# HIGHSPEED_v0_SF2-POWER.net
KiCad netlist of a schematic drawn in Altium Designer
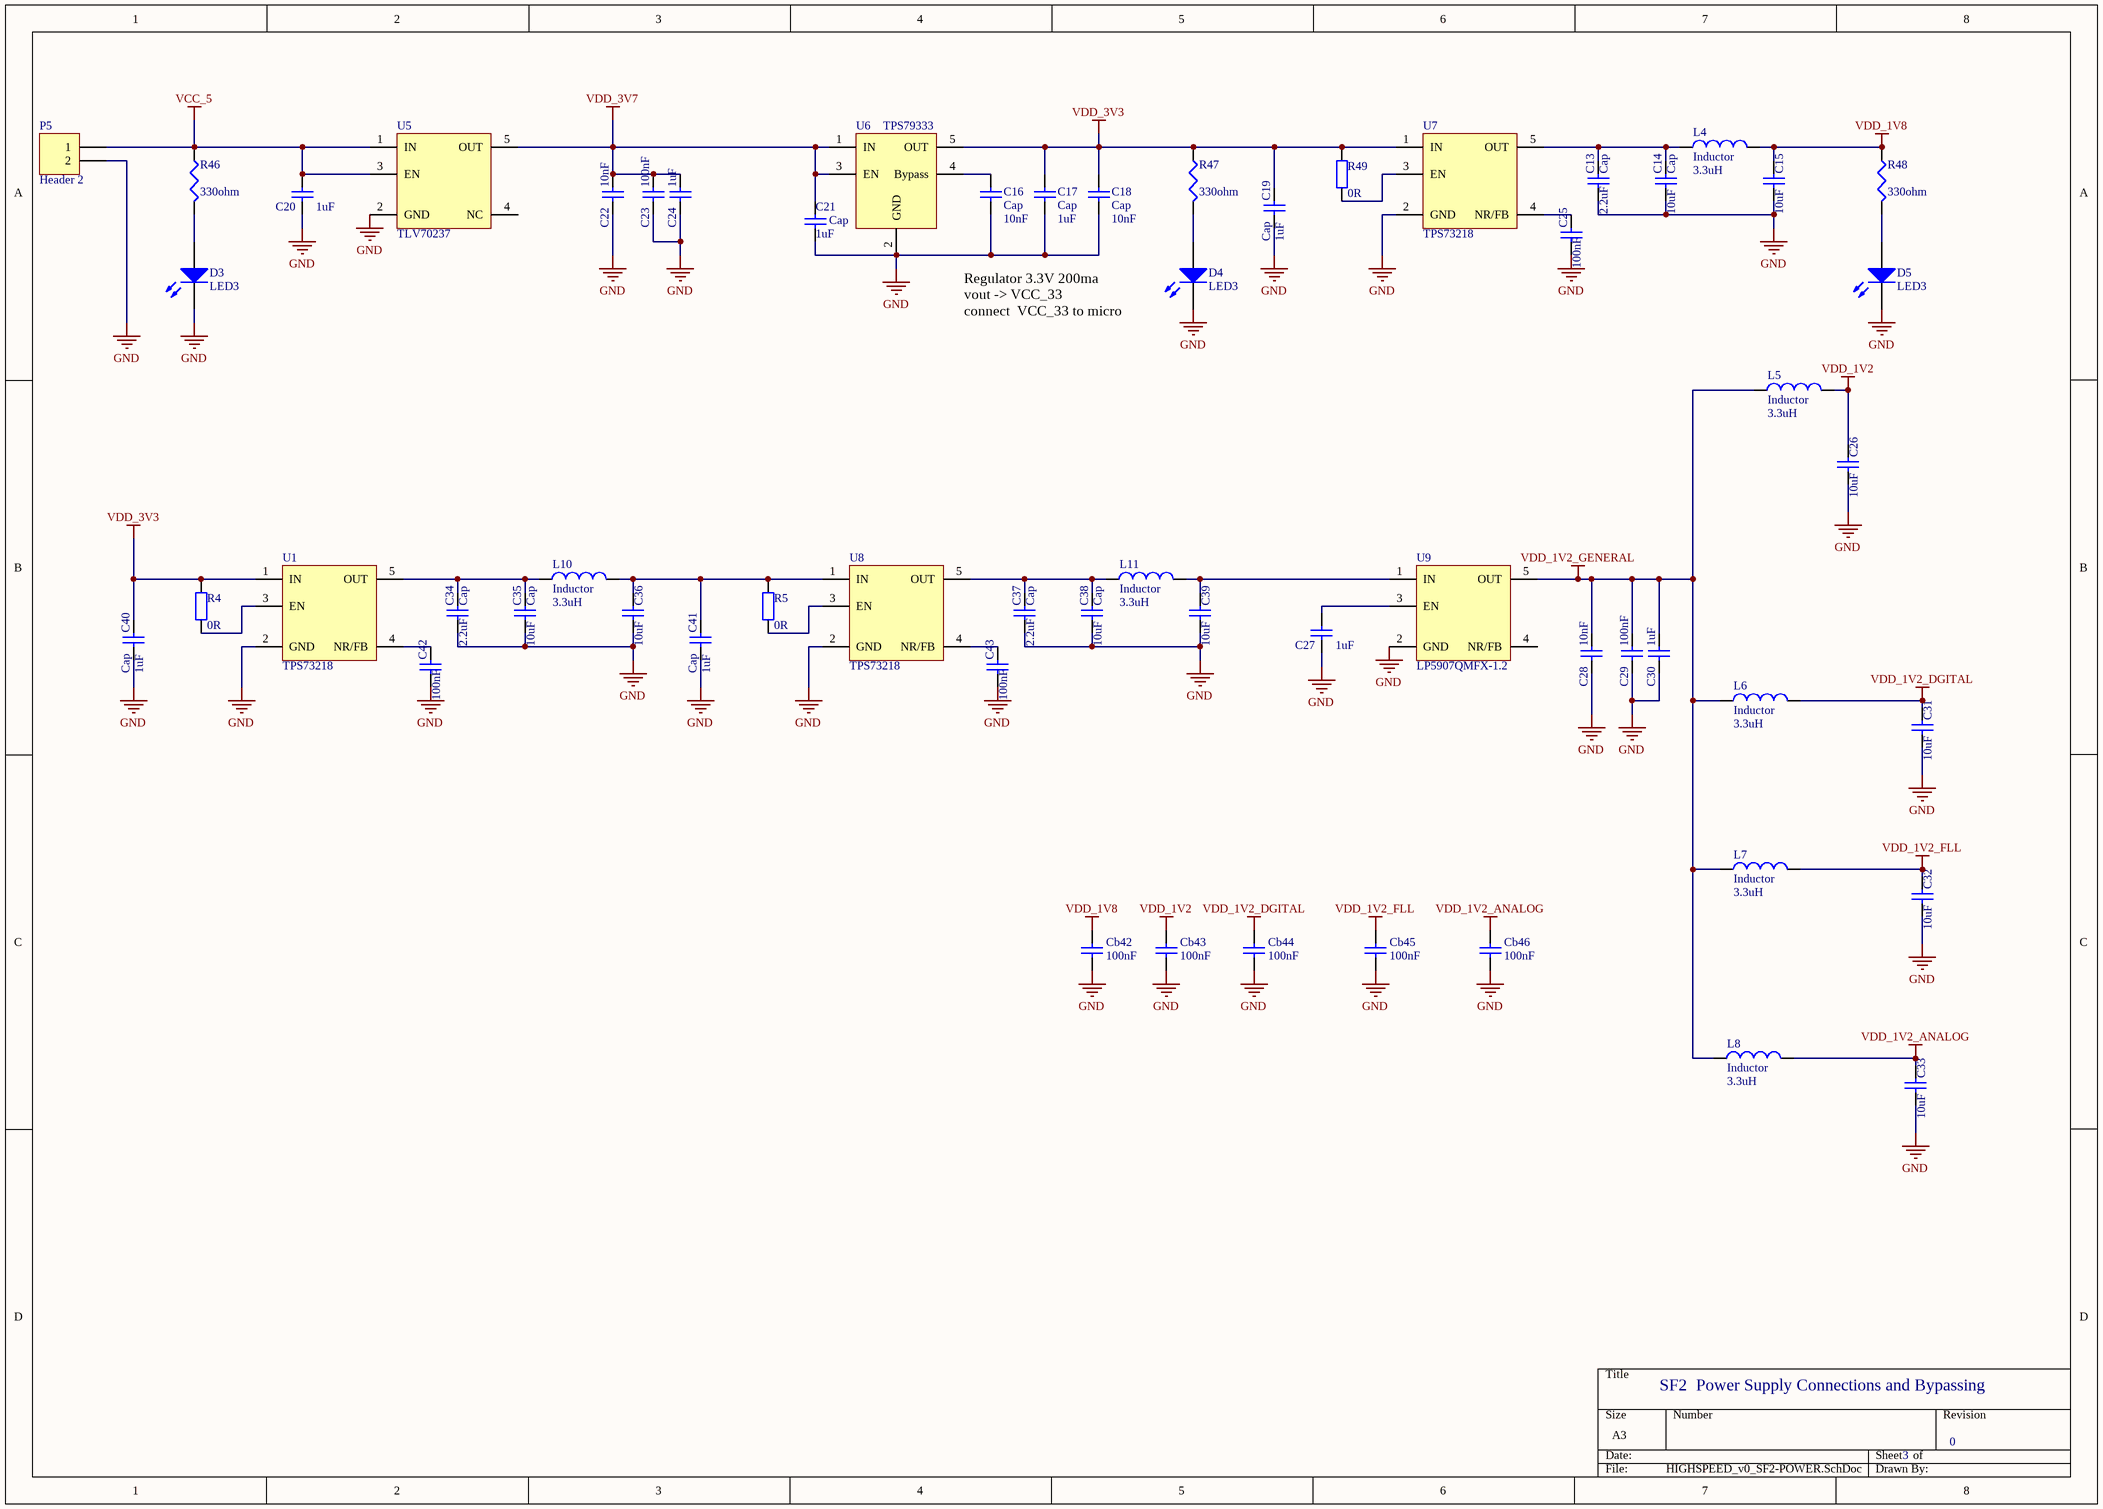
[diagram p0: HIGHSPEED_v0_SF2-POWER.SchDoc]

(export (version "E")
  (design (tool "Eeschema 10.0.6"))
  (components
    (comp (ref "C13")
      (value "Cap")
      (footprint "0603")
      (description "Capacitor")
      (fields (field (name "ALTIUM_VALUE") "2.2uF") (field (name "PUBLISHER") "Altium Limited"))
      (libsource (lib "Miscellaneous Devices") (part "Cap"))
    )
    (comp (ref "C14")
      (value "Cap")
      (footprint "0603")
      (description "Capacitor")
      (fields (field (name "ALTIUM_VALUE") "10uF") (field (name "PUBLISHER") "Altium Limited"))
      (libsource (lib "Miscellaneous Devices") (part "Cap"))
    )
    (comp (ref "C15")
      (value "10uF")
      (footprint "0603")
      (description "Capacitor")
      (fields (field (name "Comment") "Cap") (field (name "PUBLISHER") "Altium Limited"))
      (libsource (lib "Miscellaneous Devices") (part "Cap"))
    )
    (comp (ref "C16")
      (value "Cap")
      (footprint "Demo_Board_library_PCB:cap_0402_R - modified")
      (description "Capacitor")
      (fields (field (name "ALTIUM_VALUE") "10nF") (field (name "PUBLISHER") "Altium Limited"))
      (libsource (lib "Miscellaneous Devices") (part "Cap"))
    )
    (comp (ref "C17")
      (value "Cap")
      (footprint "Demo_Board_library_PCB:cap_0402_R - modified")
      (description "Capacitor")
      (fields (field (name "ALTIUM_VALUE") "1uF") (field (name "PUBLISHER") "Altium Limited"))
      (libsource (lib "Miscellaneous Devices") (part "Cap"))
    )
    (comp (ref "C18")
      (value "Cap")
      (footprint "Demo_Board_library_PCB:cap_0402_R - modified")
      (description "Capacitor")
      (fields (field (name "ALTIUM_VALUE") "10nF") (field (name "PUBLISHER") "Altium Limited"))
      (libsource (lib "Miscellaneous Devices") (part "Cap"))
    )
    (comp (ref "C19")
      (value "Cap")
      (footprint "0603")
      (description "Capacitor")
      (fields (field (name "ALTIUM_VALUE") "1uF") (field (name "PUBLISHER") "Altium Limited"))
      (libsource (lib "Miscellaneous Devices") (part "Cap"))
    )
    (comp (ref "C20")
      (value "1uF")
      (footprint "1608[0603]")
      (description "Capacitor")
      (fields (field (name "Comment") "Cap Semi") (field (name "PUBLISHER") "Altium Limited"))
      (libsource (lib "Miscellaneous Devices") (part "Cap Semi"))
    )
    (comp (ref "C21")
      (value "Cap")
      (footprint "Demo_Board_library_PCB:cap_0402_R - modified")
      (description "Capacitor")
      (fields (field (name "ALTIUM_VALUE") "1uF") (field (name "PUBLISHER") "Altium Limited"))
      (libsource (lib "Miscellaneous Devices") (part "Cap"))
    )
    (comp (ref "C22")
      (value "10nF")
      (footprint "1608[0603]")
      (description "Capacitor")
      (fields (field (name "Comment") "Cap Semi") (field (name "PUBLISHER") "Altium Limited"))
      (libsource (lib "Miscellaneous Devices") (part "Cap Semi"))
    )
    (comp (ref "C23")
      (value "100nF")
      (footprint "1608[0603]")
      (description "Capacitor")
      (fields (field (name "Comment") "Cap Semi") (field (name "PUBLISHER") "Altium Limited"))
      (libsource (lib "Miscellaneous Devices") (part "Cap Semi"))
    )
    (comp (ref "C24")
      (value "1uF")
      (footprint "1608[0603]")
      (description "Capacitor")
      (fields (field (name "Comment") "Cap Semi") (field (name "PUBLISHER") "Altium Limited"))
      (libsource (lib "Miscellaneous Devices") (part "Cap Semi"))
    )
    (comp (ref "C25")
      (value "100nF")
      (footprint "0603")
      (description "Capacitor")
      (fields (field (name "PUBLISHER") "Altium Limited"))
      (libsource (lib "Miscellaneous Devices") (part "Cap"))
    )
    (comp (ref "C26")
      (value "10uF")
      (footprint "0603")
      (description "Capacitor")
      (fields (field (name "Comment") "Cap") (field (name "PUBLISHER") "Altium Limited"))
      (libsource (lib "Miscellaneous Devices") (part "Cap"))
    )
    (comp (ref "C27")
      (value "1uF")
      (footprint "1608[0603]")
      (description "Capacitor")
      (fields (field (name "Comment") "Cap Semi") (field (name "PUBLISHER") "Altium Limited"))
      (libsource (lib "Miscellaneous Devices") (part "Cap Semi"))
    )
    (comp (ref "C28")
      (value "10nF")
      (footprint "1608[0603]")
      (description "Capacitor")
      (fields (field (name "Comment") "Cap Semi") (field (name "PUBLISHER") "Altium Limited"))
      (libsource (lib "Miscellaneous Devices") (part "Cap Semi"))
    )
    (comp (ref "C29")
      (value "100nF")
      (footprint "1608[0603]")
      (description "Capacitor")
      (fields (field (name "Comment") "Cap Semi") (field (name "PUBLISHER") "Altium Limited"))
      (libsource (lib "Miscellaneous Devices") (part "Cap Semi"))
    )
    (comp (ref "C30")
      (value "1uF")
      (footprint "1608[0603]")
      (description "Capacitor")
      (fields (field (name "Comment") "Cap Semi") (field (name "PUBLISHER") "Altium Limited"))
      (libsource (lib "Miscellaneous Devices") (part "Cap Semi"))
    )
    (comp (ref "C31")
      (value "10uF")
      (footprint "0603")
      (description "Capacitor")
      (fields (field (name "Comment") "Cap") (field (name "PUBLISHER") "Altium Limited"))
      (libsource (lib "Miscellaneous Devices") (part "Cap"))
    )
    (comp (ref "C32")
      (value "10uF")
      (footprint "0603")
      (description "Capacitor")
      (fields (field (name "Comment") "Cap") (field (name "PUBLISHER") "Altium Limited"))
      (libsource (lib "Miscellaneous Devices") (part "Cap"))
    )
    (comp (ref "C33")
      (value "10uF")
      (footprint "0603")
      (description "Capacitor")
      (fields (field (name "Comment") "Cap") (field (name "PUBLISHER") "Altium Limited"))
      (libsource (lib "Miscellaneous Devices") (part "Cap"))
    )
    (comp (ref "C34")
      (value "Cap")
      (footprint "0603")
      (description "Capacitor")
      (fields (field (name "ALTIUM_VALUE") "2.2uF") (field (name "PUBLISHER") "Altium Limited"))
      (libsource (lib "Miscellaneous Devices") (part "Cap"))
    )
    (comp (ref "C35")
      (value "Cap")
      (footprint "0603")
      (description "Capacitor")
      (fields (field (name "ALTIUM_VALUE") "10uF") (field (name "PUBLISHER") "Altium Limited"))
      (libsource (lib "Miscellaneous Devices") (part "Cap"))
    )
    (comp (ref "C36")
      (value "10uF")
      (footprint "0603")
      (description "Capacitor")
      (fields (field (name "Comment") "Cap") (field (name "PUBLISHER") "Altium Limited"))
      (libsource (lib "Miscellaneous Devices") (part "Cap"))
    )
    (comp (ref "C37")
      (value "Cap")
      (footprint "0603")
      (description "Capacitor")
      (fields (field (name "ALTIUM_VALUE") "2.2uF") (field (name "PUBLISHER") "Altium Limited"))
      (libsource (lib "Miscellaneous Devices") (part "Cap"))
    )
    (comp (ref "C38")
      (value "Cap")
      (footprint "0603")
      (description "Capacitor")
      (fields (field (name "ALTIUM_VALUE") "10uF") (field (name "PUBLISHER") "Altium Limited"))
      (libsource (lib "Miscellaneous Devices") (part "Cap"))
    )
    (comp (ref "C39")
      (value "10uF")
      (footprint "0603")
      (description "Capacitor")
      (fields (field (name "Comment") "Cap") (field (name "PUBLISHER") "Altium Limited"))
      (libsource (lib "Miscellaneous Devices") (part "Cap"))
    )
    (comp (ref "C40")
      (value "Cap")
      (footprint "0603")
      (description "Capacitor")
      (fields (field (name "ALTIUM_VALUE") "1uF") (field (name "PUBLISHER") "Altium Limited"))
      (libsource (lib "Miscellaneous Devices") (part "Cap"))
    )
    (comp (ref "C41")
      (value "Cap")
      (footprint "0603")
      (description "Capacitor")
      (fields (field (name "ALTIUM_VALUE") "1uF") (field (name "PUBLISHER") "Altium Limited"))
      (libsource (lib "Miscellaneous Devices") (part "Cap"))
    )
    (comp (ref "C42")
      (value "100nF")
      (footprint "0603")
      (description "Capacitor")
      (fields (field (name "PUBLISHER") "Altium Limited"))
      (libsource (lib "Miscellaneous Devices") (part "Cap"))
    )
    (comp (ref "C43")
      (value "100nF")
      (footprint "0603")
      (description "Capacitor")
      (fields (field (name "PUBLISHER") "Altium Limited"))
      (libsource (lib "Miscellaneous Devices") (part "Cap"))
    )
    (comp (ref "Cb42")
      (value "100nF")
      (footprint "c0603-Murata-GR")
      (description "CAP CER 22UF 10V X5R 0603")
      (fields (field (name "MANUFACTURER") "Murata") (field (name "Comment") "GRM187R61A226ME15D"))
      (libsource (lib "Custom") (part "Cap"))
    )
    (comp (ref "Cb43")
      (value "100nF")
      (footprint "c0603-Murata-GR")
      (description "CAP CER 22UF 10V X5R 0603")
      (fields (field (name "MANUFACTURER") "Murata") (field (name "Comment") "GRM187R61A226ME15D"))
      (libsource (lib "Custom") (part "Cap"))
    )
    (comp (ref "Cb44")
      (value "100nF")
      (footprint "c0603-Murata-GR")
      (description "CAP CER 22UF 10V X5R 0603")
      (fields (field (name "MANUFACTURER") "Murata") (field (name "Comment") "GRM187R61A226ME15D"))
      (libsource (lib "Custom") (part "Cap"))
    )
    (comp (ref "Cb45")
      (value "100nF")
      (footprint "c0603-Murata-GR")
      (description "CAP CER 22UF 10V X5R 0603")
      (fields (field (name "MANUFACTURER") "Murata") (field (name "Comment") "GRM187R61A226ME15D"))
      (libsource (lib "Custom") (part "Cap"))
    )
    (comp (ref "Cb46")
      (value "100nF")
      (footprint "c0603-Murata-GR")
      (description "CAP CER 22UF 10V X5R 0603")
      (fields (field (name "MANUFACTURER") "Murata") (field (name "Comment") "GRM187R61A226ME15D"))
      (libsource (lib "Custom") (part "Cap"))
    )
    (comp (ref "D3")
      (value "LED3")
      (footprint "0603")
      (description "Typical BLUE SiC LED")
      (fields (field (name "PUBLISHER") "Altium Limited"))
      (libsource (lib "Miscellaneous Devices") (part "LED3"))
    )
    (comp (ref "D4")
      (value "LED3")
      (footprint "0603")
      (description "Typical BLUE SiC LED")
      (fields (field (name "PUBLISHER") "Altium Limited"))
      (libsource (lib "Miscellaneous Devices") (part "LED3"))
    )
    (comp (ref "D5")
      (value "LED3")
      (footprint "0603")
      (description "Typical BLUE SiC LED")
      (fields (field (name "PUBLISHER") "Altium Limited"))
      (libsource (lib "Miscellaneous Devices") (part "LED3"))
    )
    (comp (ref "L4")
      (value "Inductor")
      (footprint "1608[0603]")
      (fields (field (name "ALTIUM_VALUE") "3.3uH") (field (name "PUBLISHER") "Altium Limited"))
      (libsource (lib "Miscellaneous Devices") (part "Inductor"))
    )
    (comp (ref "L5")
      (value "Inductor")
      (footprint "1608[0603]")
      (fields (field (name "ALTIUM_VALUE") "3.3uH") (field (name "PUBLISHER") "Altium Limited"))
      (libsource (lib "Miscellaneous Devices") (part "Inductor"))
    )
    (comp (ref "L6")
      (value "Inductor")
      (footprint "1608[0603]")
      (fields (field (name "ALTIUM_VALUE") "3.3uH") (field (name "PUBLISHER") "Altium Limited"))
      (libsource (lib "Miscellaneous Devices") (part "Inductor"))
    )
    (comp (ref "L7")
      (value "Inductor")
      (footprint "1608[0603]")
      (fields (field (name "ALTIUM_VALUE") "3.3uH") (field (name "PUBLISHER") "Altium Limited"))
      (libsource (lib "Miscellaneous Devices") (part "Inductor"))
    )
    (comp (ref "L8")
      (value "Inductor")
      (footprint "1608[0603]")
      (fields (field (name "ALTIUM_VALUE") "3.3uH") (field (name "PUBLISHER") "Altium Limited"))
      (libsource (lib "Miscellaneous Devices") (part "Inductor"))
    )
    (comp (ref "L10")
      (value "Inductor")
      (footprint "1608[0603]")
      (fields (field (name "ALTIUM_VALUE") "3.3uH") (field (name "PUBLISHER") "Altium Limited"))
      (libsource (lib "Miscellaneous Devices") (part "Inductor"))
    )
    (comp (ref "L11")
      (value "Inductor")
      (footprint "1608[0603]")
      (fields (field (name "ALTIUM_VALUE") "3.3uH") (field (name "PUBLISHER") "Altium Limited"))
      (libsource (lib "Miscellaneous Devices") (part "Inductor"))
    )
    (comp (ref "P5")
      (value "Header 2")
      (footprint "HDR1X2")
      (description "Header, 2-Pin")
      (fields (field (name "PUBLISHER") "Altium Limited"))
      (libsource (lib "Miscellaneous Connectors") (part "Header 2"))
    )
    (comp (ref "R4")
      (value "0R")
      (footprint "0603")
      (description "Resistor")
      (fields (field (name "PUBLISHER") "Altium Limited"))
      (libsource (lib "Miscellaneous Devices") (part "Res2"))
    )
    (comp (ref "R5")
      (value "0R")
      (footprint "0603")
      (description "Resistor")
      (fields (field (name "PUBLISHER") "Altium Limited"))
      (libsource (lib "Miscellaneous Devices") (part "Res2"))
    )
    (comp (ref "R46")
      (value "330ohm")
      (footprint "res_0402_R - modified")
      (description "Resistor")
      (fields (field (name "Comment") "Res3") (field (name "PUBLISHER") "Altium Limited"))
      (libsource (lib "Miscellaneous Devices") (part "Res3"))
    )
    (comp (ref "R47")
      (value "330ohm")
      (footprint "res_0402_R - modified")
      (description "Resistor")
      (fields (field (name "Comment") "Res3") (field (name "PUBLISHER") "Altium Limited"))
      (libsource (lib "Miscellaneous Devices") (part "Res3"))
    )
    (comp (ref "R48")
      (value "330ohm")
      (footprint "res_0402_R - modified")
      (description "Resistor")
      (fields (field (name "Comment") "Res3") (field (name "PUBLISHER") "Altium Limited"))
      (libsource (lib "Miscellaneous Devices") (part "Res3"))
    )
    (comp (ref "R49")
      (value "0R")
      (footprint "0603")
      (description "Resistor")
      (fields (field (name "PUBLISHER") "Altium Limited"))
      (libsource (lib "Miscellaneous Devices") (part "Res2"))
    )
    (comp (ref "U1")
      (value "TPS73218")
      (footprint "Demo_Board_library_PCB:SOT23__DDC__(R - PDSO-  G5)")
      (description "Linear Regulator")
      (libsource (lib "Demo_Board_library_SCH") (part "TPS73218"))
    )
    (comp (ref "U5")
      (value "TLV70237")
      (footprint "Demo_Board_library_PCB:SOT23__DDC__(R - PDSO-  G5)")
      (description "Linear Regulator")
      (libsource (lib "Demo_Board_library_SCH") (part "TLV70237"))
    )
    (comp (ref "U6")
      (value "TPS79333")
      (footprint "Demo_Board_library_PCB:SOT_23__DBV_(R - PDSO - G5)")
      (description "Regulator")
      (libsource (lib "Demo_Board_library_SCH") (part "TPS79333"))
    )
    (comp (ref "U7")
      (value "TPS73218")
      (footprint "Demo_Board_library_PCB:SOT23__DDC__(R - PDSO-  G5)")
      (description "Linear Regulator")
      (libsource (lib "Demo_Board_library_SCH") (part "TPS73218"))
    )
    (comp (ref "U8")
      (value "TPS73218")
      (footprint "Demo_Board_library_PCB:SOT23__DDC__(R - PDSO-  G5)")
      (description "Linear Regulator")
      (libsource (lib "Demo_Board_library_SCH") (part "TPS73218"))
    )
    (comp (ref "U9")
      (value "LP5907QMFX-1.2")
      (footprint "Demo_Board_library_PCB:SOT23__DDC__(R - PDSO-  G5)")
      (description "Linear Regulator")
      (libsource (lib "Demo_Board_library_SCH") (part "LP5907QMFX-1.2"))
    )
  )
  (nets
    (net (code "1") (name "GND") (class "Default")
      (node (ref "C13") (pin "2") (pinfunction "2_2") (pintype "passive"))
      (node (ref "C14") (pin "2") (pinfunction "2_2") (pintype "passive"))
      (node (ref "C15") (pin "2") (pinfunction "2_2") (pintype "passive"))
      (node (ref "C16") (pin "1") (pinfunction "1_1") (pintype "passive"))
      (node (ref "C17") (pin "2") (pinfunction "2_2") (pintype "passive"))
      (node (ref "C18") (pin "1") (pinfunction "1_1") (pintype "passive"))
      (node (ref "C19") (pin "2") (pinfunction "2_2") (pintype "passive"))
      (node (ref "C20") (pin "1") (pinfunction "1_1") (pintype "passive"))
      (node (ref "C21") (pin "1") (pinfunction "1_1") (pintype "passive"))
      (node (ref "C22") (pin "1") (pinfunction "1_1") (pintype "passive"))
      (node (ref "C23") (pin "1") (pinfunction "1_1") (pintype "passive"))
      (node (ref "C24") (pin "1") (pinfunction "1_1") (pintype "passive"))
      (node (ref "C25") (pin "2") (pinfunction "2_2") (pintype "passive"))
      (node (ref "C26") (pin "2") (pinfunction "2_2") (pintype "passive"))
      (node (ref "C27") (pin "1") (pinfunction "1_1") (pintype "passive"))
      (node (ref "C28") (pin "1") (pinfunction "1_1") (pintype "passive"))
      (node (ref "C29") (pin "1") (pinfunction "1_1") (pintype "passive"))
      (node (ref "C30") (pin "1") (pinfunction "1_1") (pintype "passive"))
      (node (ref "C31") (pin "2") (pinfunction "2_2") (pintype "passive"))
      (node (ref "C32") (pin "2") (pinfunction "2_2") (pintype "passive"))
      (node (ref "C33") (pin "2") (pinfunction "2_2") (pintype "passive"))
      (node (ref "C34") (pin "2") (pinfunction "2_2") (pintype "passive"))
      (node (ref "C35") (pin "2") (pinfunction "2_2") (pintype "passive"))
      (node (ref "C36") (pin "2") (pinfunction "2_2") (pintype "passive"))
      (node (ref "C37") (pin "2") (pinfunction "2_2") (pintype "passive"))
      (node (ref "C38") (pin "2") (pinfunction "2_2") (pintype "passive"))
      (node (ref "C39") (pin "2") (pinfunction "2_2") (pintype "passive"))
      (node (ref "C40") (pin "2") (pinfunction "2_2") (pintype "passive"))
      (node (ref "C41") (pin "2") (pinfunction "2_2") (pintype "passive"))
      (node (ref "C42") (pin "2") (pinfunction "2_2") (pintype "passive"))
      (node (ref "C43") (pin "2") (pinfunction "2_2") (pintype "passive"))
      (node (ref "Cb42") (pin "1") (pinfunction "1_1") (pintype "passive"))
      (node (ref "Cb43") (pin "1") (pinfunction "1_1") (pintype "passive"))
      (node (ref "Cb44") (pin "1") (pinfunction "1_1") (pintype "passive"))
      (node (ref "Cb45") (pin "1") (pinfunction "1_1") (pintype "passive"))
      (node (ref "Cb46") (pin "1") (pinfunction "1_1") (pintype "passive"))
      (node (ref "D3") (pin "2") (pinfunction "K_2") (pintype "passive"))
      (node (ref "D4") (pin "2") (pinfunction "K_2") (pintype "passive"))
      (node (ref "D5") (pin "2") (pinfunction "K_2") (pintype "passive"))
      (node (ref "P5") (pin "2") (pinfunction "2_2") (pintype "passive"))
      (node (ref "U1") (pin "2") (pinfunction "GND_2") (pintype "passive"))
      (node (ref "U5") (pin "2") (pinfunction "GND_2") (pintype "passive"))
      (node (ref "U6") (pin "2") (pinfunction "GND_2") (pintype "passive"))
      (node (ref "U7") (pin "2") (pinfunction "GND_2") (pintype "passive"))
      (node (ref "U8") (pin "2") (pinfunction "GND_2") (pintype "passive"))
      (node (ref "U9") (pin "2") (pinfunction "GND_2") (pintype "passive"))
    )
    (net (code "2") (name "Net-(D3-A)") (class "Default")
      (node (ref "D3") (pin "1") (pinfunction "A_1") (pintype "passive"))
      (node (ref "R46") (pin "2") (pinfunction "2_2") (pintype "passive"))
    )
    (net (code "3") (name "Net-(D4-A)") (class "Default")
      (node (ref "D4") (pin "1") (pinfunction "A_1") (pintype "passive"))
      (node (ref "R47") (pin "2") (pinfunction "2_2") (pintype "passive"))
    )
    (net (code "4") (name "Net-(D5-A)") (class "Default")
      (node (ref "D5") (pin "1") (pinfunction "A_1") (pintype "passive"))
      (node (ref "R48") (pin "2") (pinfunction "2_2") (pintype "passive"))
    )
    (net (code "5") (name "Net-(U1-EN)") (class "Default")
      (node (ref "R4") (pin "1") (pinfunction "1_1") (pintype "passive"))
      (node (ref "U1") (pin "3") (pinfunction "EN_3") (pintype "passive"))
    )
    (net (code "6") (name "Net-(U1-NR{slash}FB)") (class "Default")
      (node (ref "C42") (pin "1") (pinfunction "1_1") (pintype "passive"))
      (node (ref "U1") (pin "4") (pinfunction "NR/FB_4") (pintype "passive"))
    )
    (net (code "7") (name "Net-(U1-OUT)") (class "Default")
      (node (ref "C34") (pin "1") (pinfunction "1_1") (pintype "passive"))
      (node (ref "C35") (pin "1") (pinfunction "1_1") (pintype "passive"))
      (node (ref "L10") (pin "1") (pinfunction "1_1") (pintype "passive"))
      (node (ref "U1") (pin "5") (pinfunction "OUT_5") (pintype "passive"))
    )
    (net (code "8") (name "Net-(U6-Bypass)") (class "Default")
      (node (ref "C16") (pin "2") (pinfunction "2_2") (pintype "passive"))
      (node (ref "U6") (pin "4") (pinfunction "Bypass_4") (pintype "passive"))
    )
    (net (code "9") (name "Net-(U7-EN)") (class "Default")
      (node (ref "R49") (pin "1") (pinfunction "1_1") (pintype "passive"))
      (node (ref "U7") (pin "3") (pinfunction "EN_3") (pintype "passive"))
    )
    (net (code "10") (name "Net-(U7-NR{slash}FB)") (class "Default")
      (node (ref "C25") (pin "1") (pinfunction "1_1") (pintype "passive"))
      (node (ref "U7") (pin "4") (pinfunction "NR/FB_4") (pintype "passive"))
    )
    (net (code "11") (name "Net-(U7-OUT)") (class "Default")
      (node (ref "C13") (pin "1") (pinfunction "1_1") (pintype "passive"))
      (node (ref "C14") (pin "1") (pinfunction "1_1") (pintype "passive"))
      (node (ref "L4") (pin "1") (pinfunction "1_1") (pintype "passive"))
      (node (ref "U7") (pin "5") (pinfunction "OUT_5") (pintype "passive"))
    )
    (net (code "12") (name "Net-(U8-EN)") (class "Default")
      (node (ref "R5") (pin "1") (pinfunction "1_1") (pintype "passive"))
      (node (ref "U8") (pin "3") (pinfunction "EN_3") (pintype "passive"))
    )
    (net (code "13") (name "Net-(U8-IN)") (class "Default")
      (node (ref "C36") (pin "1") (pinfunction "1_1") (pintype "passive"))
      (node (ref "C41") (pin "1") (pinfunction "1_1") (pintype "passive"))
      (node (ref "L10") (pin "2") (pinfunction "2_2") (pintype "passive"))
      (node (ref "R5") (pin "2") (pinfunction "2_2") (pintype "passive"))
      (node (ref "U8") (pin "1") (pinfunction "IN_1") (pintype "passive"))
    )
    (net (code "14") (name "Net-(U8-NR{slash}FB)") (class "Default")
      (node (ref "C43") (pin "1") (pinfunction "1_1") (pintype "passive"))
      (node (ref "U8") (pin "4") (pinfunction "NR/FB_4") (pintype "passive"))
    )
    (net (code "15") (name "Net-(U8-OUT)") (class "Default")
      (node (ref "C37") (pin "1") (pinfunction "1_1") (pintype "passive"))
      (node (ref "C38") (pin "1") (pinfunction "1_1") (pintype "passive"))
      (node (ref "L11") (pin "1") (pinfunction "1_1") (pintype "passive"))
      (node (ref "U8") (pin "5") (pinfunction "OUT_5") (pintype "passive"))
    )
    (net (code "16") (name "Net-(U9-EN)") (class "Default")
      (node (ref "C27") (pin "2") (pinfunction "2_2") (pintype "passive"))
      (node (ref "U9") (pin "3") (pinfunction "EN_3") (pintype "passive"))
    )
    (net (code "17") (name "Net-(U9-IN)") (class "Default")
      (node (ref "C39") (pin "1") (pinfunction "1_1") (pintype "passive"))
      (node (ref "L11") (pin "2") (pinfunction "2_2") (pintype "passive"))
      (node (ref "U9") (pin "1") (pinfunction "IN_1") (pintype "passive"))
    )
    (net (code "18") (name "VCC_5") (class "Default")
      (node (ref "C20") (pin "2") (pinfunction "2_2") (pintype "passive"))
      (node (ref "P5") (pin "1") (pinfunction "1_1") (pintype "passive"))
      (node (ref "R46") (pin "1") (pinfunction "1_1") (pintype "passive"))
      (node (ref "U5") (pin "1") (pinfunction "IN_1") (pintype "passive"))
      (node (ref "U5") (pin "3") (pinfunction "EN_3") (pintype "passive"))
    )
    (net (code "19") (name "VDD_1V2") (class "Default")
      (node (ref "C26") (pin "1") (pinfunction "1_1") (pintype "passive"))
      (node (ref "Cb43") (pin "2") (pinfunction "2_2") (pintype "passive"))
      (node (ref "L5") (pin "2") (pinfunction "2_2") (pintype "passive"))
    )
    (net (code "20") (name "VDD_1V2_ANALOG") (class "Default")
      (node (ref "C33") (pin "1") (pinfunction "1_1") (pintype "passive"))
      (node (ref "Cb46") (pin "2") (pinfunction "2_2") (pintype "passive"))
      (node (ref "L8") (pin "2") (pinfunction "2_2") (pintype "passive"))
    )
    (net (code "21") (name "VDD_1V2_DGITAL") (class "Default")
      (node (ref "C31") (pin "1") (pinfunction "1_1") (pintype "passive"))
      (node (ref "Cb44") (pin "2") (pinfunction "2_2") (pintype "passive"))
      (node (ref "L6") (pin "2") (pinfunction "2_2") (pintype "passive"))
    )
    (net (code "22") (name "VDD_1V2_FLL") (class "Default")
      (node (ref "C32") (pin "1") (pinfunction "1_1") (pintype "passive"))
      (node (ref "Cb45") (pin "2") (pinfunction "2_2") (pintype "passive"))
      (node (ref "L7") (pin "2") (pinfunction "2_2") (pintype "passive"))
    )
    (net (code "23") (name "VDD_1V2_GENERAL") (class "Default")
      (node (ref "C28") (pin "2") (pinfunction "2_2") (pintype "passive"))
      (node (ref "C29") (pin "2") (pinfunction "2_2") (pintype "passive"))
      (node (ref "C30") (pin "2") (pinfunction "2_2") (pintype "passive"))
      (node (ref "L5") (pin "1") (pinfunction "1_1") (pintype "passive"))
      (node (ref "L6") (pin "1") (pinfunction "1_1") (pintype "passive"))
      (node (ref "L7") (pin "1") (pinfunction "1_1") (pintype "passive"))
      (node (ref "L8") (pin "1") (pinfunction "1_1") (pintype "passive"))
      (node (ref "U9") (pin "5") (pinfunction "OUT_5") (pintype "passive"))
    )
    (net (code "24") (name "VDD_1V8") (class "Default")
      (node (ref "C15") (pin "1") (pinfunction "1_1") (pintype "passive"))
      (node (ref "Cb42") (pin "2") (pinfunction "2_2") (pintype "passive"))
      (node (ref "L4") (pin "2") (pinfunction "2_2") (pintype "passive"))
      (node (ref "R48") (pin "1") (pinfunction "1_1") (pintype "passive"))
    )
    (net (code "25") (name "VDD_3V3") (class "Default")
      (node (ref "C17") (pin "1") (pinfunction "1_1") (pintype "passive"))
      (node (ref "C18") (pin "2") (pinfunction "2_2") (pintype "passive"))
      (node (ref "C19") (pin "1") (pinfunction "1_1") (pintype "passive"))
      (node (ref "C40") (pin "1") (pinfunction "1_1") (pintype "passive"))
      (node (ref "R4") (pin "2") (pinfunction "2_2") (pintype "passive"))
      (node (ref "R47") (pin "1") (pinfunction "1_1") (pintype "passive"))
      (node (ref "R49") (pin "2") (pinfunction "2_2") (pintype "passive"))
      (node (ref "U1") (pin "1") (pinfunction "IN_1") (pintype "passive"))
      (node (ref "U6") (pin "5") (pinfunction "OUT_5") (pintype "passive"))
      (node (ref "U7") (pin "1") (pinfunction "IN_1") (pintype "passive"))
    )
    (net (code "26") (name "VDD_3V7") (class "Default")
      (node (ref "C21") (pin "2") (pinfunction "2_2") (pintype "passive"))
      (node (ref "C22") (pin "2") (pinfunction "2_2") (pintype "passive"))
      (node (ref "C23") (pin "2") (pinfunction "2_2") (pintype "passive"))
      (node (ref "C24") (pin "2") (pinfunction "2_2") (pintype "passive"))
      (node (ref "U5") (pin "5") (pinfunction "OUT_5") (pintype "passive"))
      (node (ref "U6") (pin "1") (pinfunction "IN_1") (pintype "passive"))
      (node (ref "U6") (pin "3") (pinfunction "EN_3") (pintype "passive"))
    )
    (net (code "27") (name "unconnected-(U5-NC-Pad4)") (class "Default")
      (node (ref "U5") (pin "4") (pinfunction "NC_4") (pintype "passive"))
    )
    (net (code "28") (name "unconnected-(U9-NR{slash}FB-Pad4)") (class "Default")
      (node (ref "U9") (pin "4") (pinfunction "NR/FB_4") (pintype "passive"))
    )
  )
)
